# GSMLift.net
KiCad netlist of a schematic drawn in Altium Designer
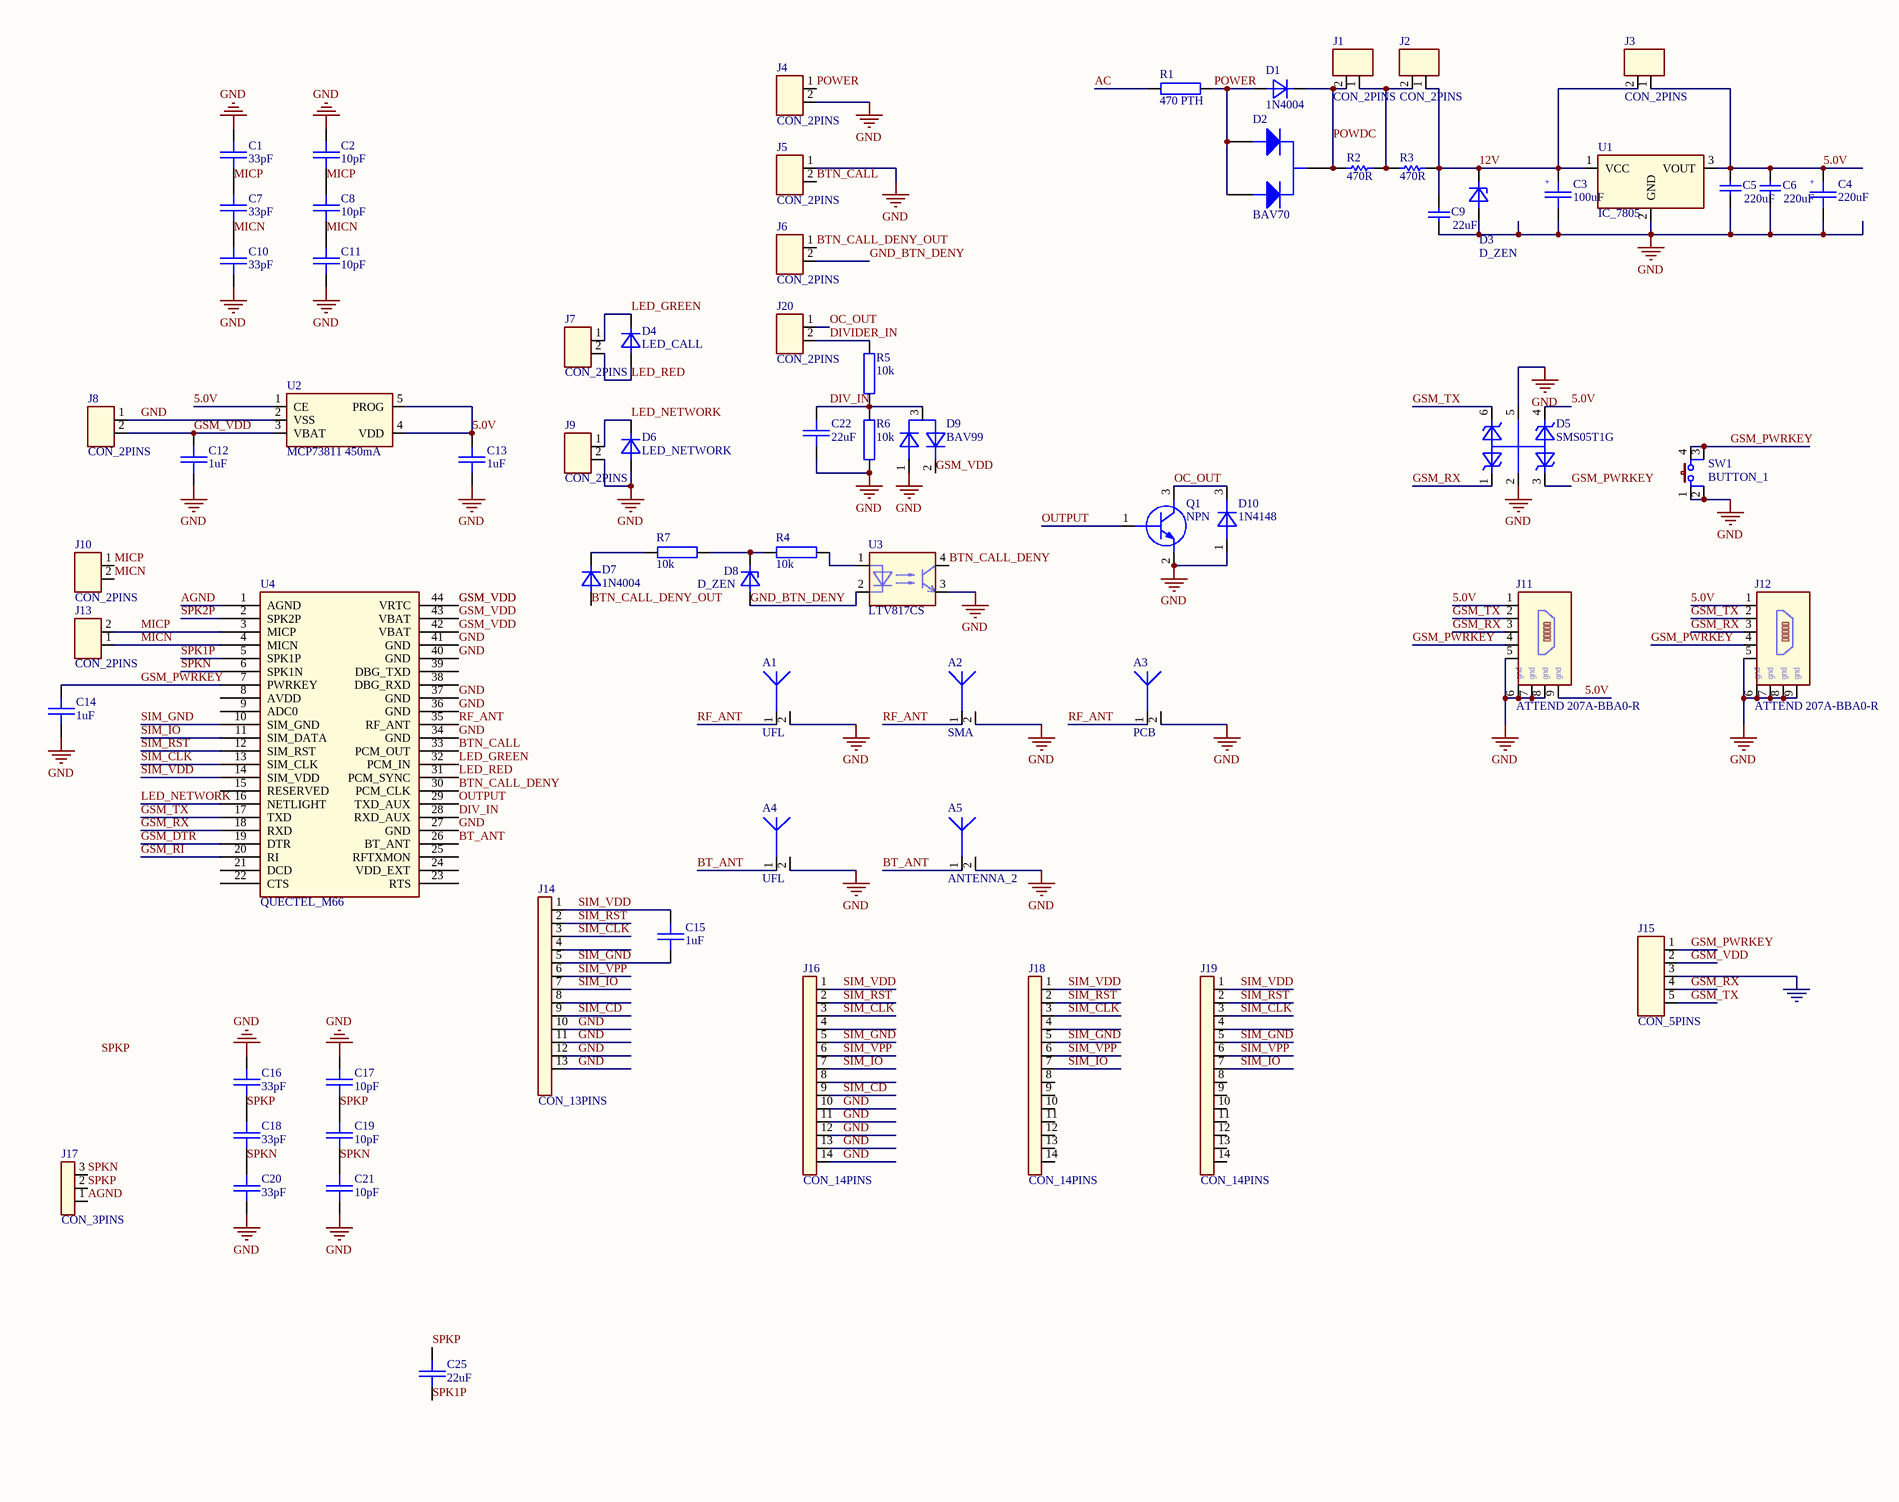
[diagram p0: GSMLift.SchDoc, left]
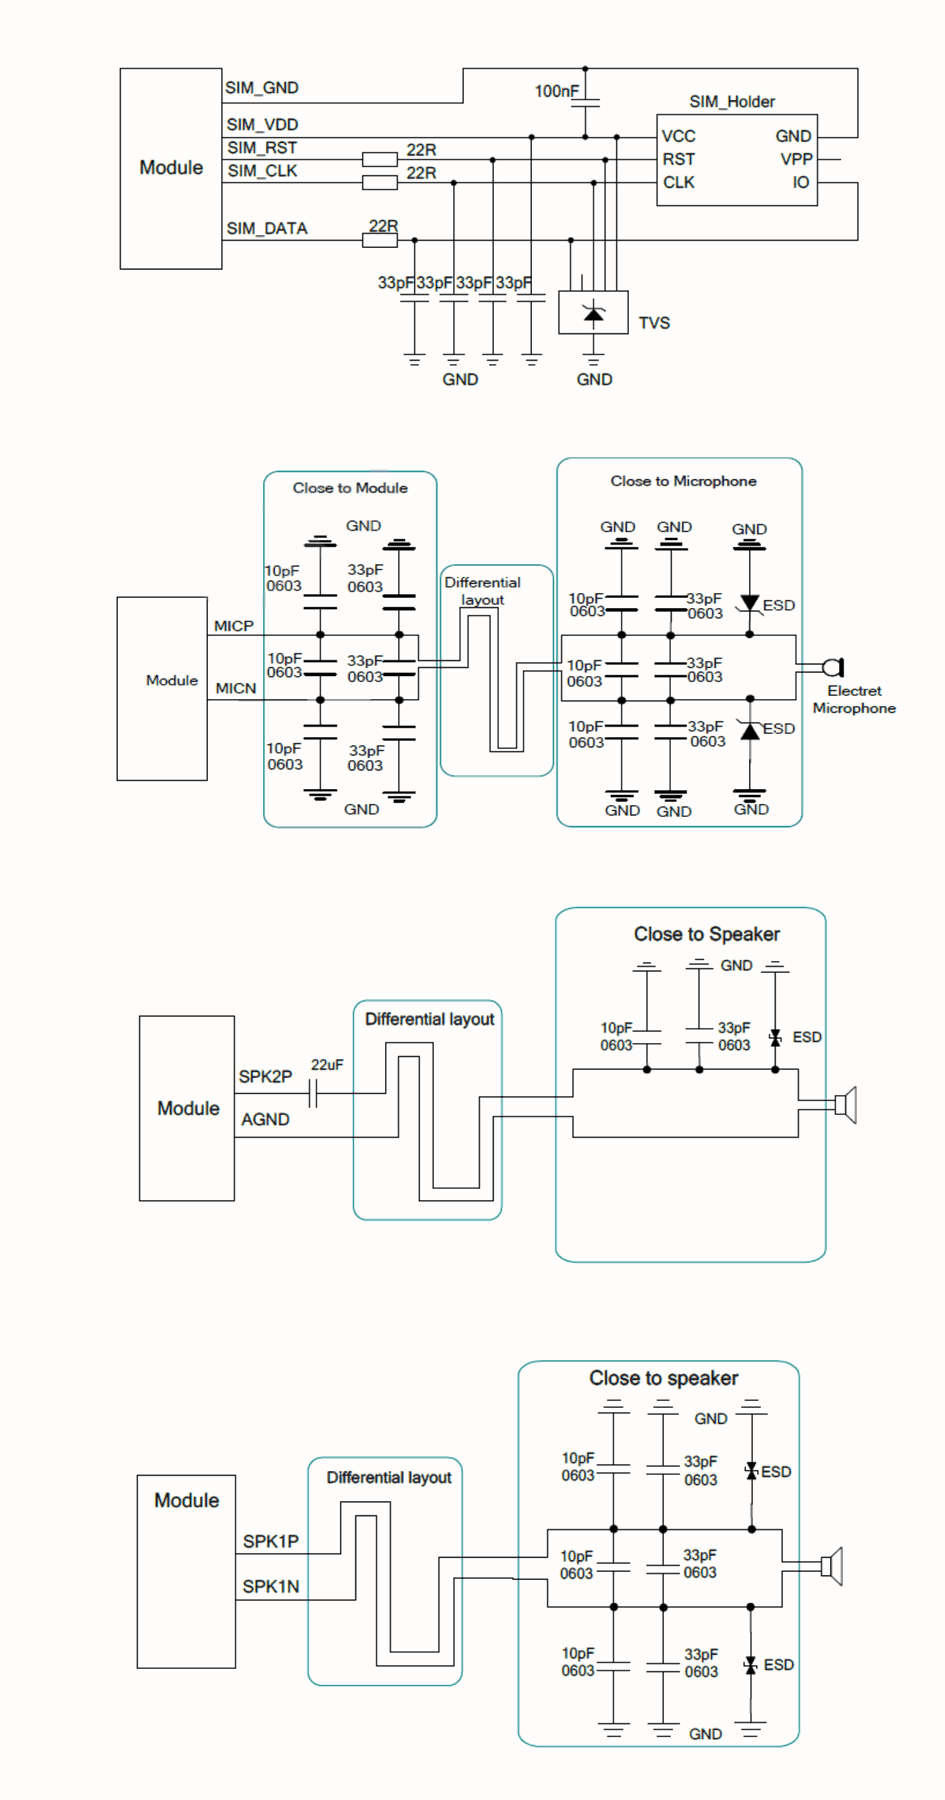
[diagram p1: GSMLift.SchDoc, right]

(export (version "E")
  (design (tool "Eeschema 10.0.6"))
  (components
    (comp (ref "A1")
      (value "UFL")
      (footprint "SMD_CON_ANTENNA_UFL")
      (libsource (lib "DLV") (part "ANTENNA_2"))
    )
    (comp (ref "A2")
      (value "SMA")
      (footprint "SMD_CON_ANTENNA_SMA")
      (libsource (lib "DLV") (part "ANTENNA_2"))
    )
    (comp (ref "A3")
      (value "PCB")
      (footprint "SMD_CON_ANTENNA_GSM_PCB_INV")
      (libsource (lib "DLV") (part "ANTENNA_2"))
    )
    (comp (ref "A4")
      (value "UFL")
      (footprint "SMD_CON_ANTENNA_UFL")
      (libsource (lib "DLV") (part "ANTENNA_2"))
    )
    (comp (ref "A5")
      (value "ANTENNA_2")
      (footprint "SMD_CON_ANTENNA_BT_PCB")
      (libsource (lib "DLV") (part "ANTENNA_2"))
    )
    (comp (ref "C1") (value "33pF") (footprint "SMD_0603_CAPC1608X95N") (libsource (lib "DLV") (part "C")))
    (comp (ref "C2") (value "10pF") (footprint "SMD_0603_CAPC1608X95N") (libsource (lib "DLV") (part "C")))
    (comp (ref "C3") (value "100uF") (footprint "SMD_CAPAE1030X1050N") (libsource (lib "DLV") (part "C_POL")))
    (comp (ref "C4") (value "220uF") (footprint "SMD_CAPAE1030X1050N") (libsource (lib "DLV") (part "C_POL")))
    (comp (ref "C5")
      (value "220uF")
      (footprint "SMD_1210_CAPC3225X279N")
      (description "CL32A227MQVNNNE 220UF 6.3V 20% X5R 1210")
      (fields (field (name "PUBLISHER") "Altium Limited"))
      (libsource (lib "Miscellaneous Devices") (part "Cap Semi"))
    )
    (comp (ref "C6")
      (value "220uF")
      (footprint "SMD_1210_CAPC3225X279N")
      (description "CL32A227MQVNNNE 220UF 6.3V 20% X5R 1210")
      (fields (field (name "PUBLISHER") "Altium Limited"))
      (libsource (lib "Miscellaneous Devices") (part "Cap Semi"))
    )
    (comp (ref "C7") (value "33pF") (footprint "SMD_0603_CAPC1608X95N") (libsource (lib "DLV") (part "C")))
    (comp (ref "C8") (value "10pF") (footprint "SMD_0603_CAPC1608X95N") (libsource (lib "DLV") (part "C")))
    (comp (ref "C9")
      (value "22uF")
      (footprint "SMD_1210_CAPC3225X279N")
      (description "CL32A227MQVNNNE 220UF 6.3V 20% X5R 1210")
      (fields (field (name "PUBLISHER") "Altium Limited"))
      (libsource (lib "Miscellaneous Devices") (part "Cap Semi"))
    )
    (comp (ref "C10") (value "33pF") (footprint "SMD_0603_CAPC1608X95N") (libsource (lib "DLV") (part "C")))
    (comp (ref "C11") (value "10pF") (footprint "SMD_0603_CAPC1608X95N") (libsource (lib "DLV") (part "C")))
    (comp (ref "C12") (value "1uF") (footprint "SMD_0603_CAPC1608X95N") (libsource (lib "DLV") (part "C")))
    (comp (ref "C13") (value "1uF") (footprint "SMD_0603_CAPC1608X95N") (libsource (lib "DLV") (part "C")))
    (comp (ref "C14") (value "1uF") (footprint "SMD_0603_CAPC1608X95N") (libsource (lib "DLV") (part "C")))
    (comp (ref "C15") (value "1uF") (footprint "SMD_0603_CAPC1608X95N") (libsource (lib "DLV") (part "C")))
    (comp (ref "C16") (value "33pF") (footprint "SMD_0603_CAPC1608X95N") (libsource (lib "DLV") (part "C")))
    (comp (ref "C17") (value "10pF") (footprint "SMD_0603_CAPC1608X95N") (libsource (lib "DLV") (part "C")))
    (comp (ref "C18") (value "33pF") (footprint "SMD_0603_CAPC1608X95N") (libsource (lib "DLV") (part "C")))
    (comp (ref "C19") (value "10pF") (footprint "SMD_0603_CAPC1608X95N") (libsource (lib "DLV") (part "C")))
    (comp (ref "C20") (value "33pF") (footprint "SMD_0603_CAPC1608X95N") (libsource (lib "DLV") (part "C")))
    (comp (ref "C21") (value "10pF") (footprint "SMD_0603_CAPC1608X95N") (libsource (lib "DLV") (part "C")))
    (comp (ref "C22") (value "22uF") (footprint "SMD_0805_CAPC2012X95N") (libsource (lib "DLV") (part "C")))
    (comp (ref "C25") (value "22uF") (footprint "SMD_0603_CAPC1608X95N") (libsource (lib "DLV") (part "C")))
    (comp (ref "D1")
      (value "1N4004")
      (footprint "SMD_DO214AC_SMA")
      (libsource (lib "EPIQ_DND_CIS_Library") (part "D"))
    )
    (comp (ref "D2")
      (value "BAV70")
      (footprint "SMD_SOT23_SOT95P240X120-3N")
      (libsource (lib "Devices") (part "DUAL DIODE BAV70"))
    )
    (comp (ref "D3")
      (value "D_ZEN")
      (footprint "SMD_DO214AC_SMA")
      (libsource (lib "EPIQ_DND_CIS_Library") (part "D_ZEN"))
    )
    (comp (ref "D4")
      (value "LED_CALL")
      (footprint "SMD_0805_LED2012X100N")
      (libsource (lib "DLV") (part "D"))
    )
    (comp (ref "D5")
      (value "SMS05T1G")
      (footprint "SMD_SOT95P280X145-6N-W")
      (description "4 IO lines TVS")
      (libsource (lib "BitCoin") (part "D_TVS_QUAD_C1AA2AA5C3C4C6"))
    )
    (comp (ref "D6")
      (value "LED_NETWORK")
      (footprint "SMD_0805_LED2012X100N")
      (libsource (lib "DLV") (part "D"))
    )
    (comp (ref "D7")
      (value "1N4004")
      (footprint "SMD_DO214AC_SMA")
      (libsource (lib "EPIQ_DND_CIS_Library") (part "D"))
    )
    (comp (ref "D8")
      (value "D_ZEN")
      (footprint "SMD_DO214AC_SMA")
      (libsource (lib "EPIQ_DND_CIS_Library") (part "D_ZEN"))
    )
    (comp (ref "D9")
      (value "BAV99")
      (footprint "SMD_SOT23_SOT95P240X120-3N")
      (libsource (lib "DLV") (part "D_DUAL_A1C2AC3"))
    )
    (comp (ref "D10")
      (value "1N4148")
      (footprint "SMD_SOT23_SOT95P240X120-3N")
      (libsource (lib "DLV") (part "D_A1C3"))
    )
    (comp (ref "J1")
      (value "CON_2PINS")
      (footprint "PTH_HDRV02W64P254_1X02")
      (libsource (lib "") (part "CON_2PINS_1"))
    )
    (comp (ref "J2")
      (value "CON_2PINS")
      (footprint "PTH_HDRV02W64P254_1X02")
      (libsource (lib "") (part "CON_2PINS_1"))
    )
    (comp (ref "J3")
      (value "CON_2PINS")
      (footprint "PTH_HDRV02W64P254_1X02")
      (libsource (lib "") (part "CON_2PINS_1"))
    )
    (comp (ref "J4")
      (value "CON_2PINS")
      (footprint "PTH_HDRV02W11060P500_1X02")
      (libsource (lib "DLV") (part "CON_2PINS"))
    )
    (comp (ref "J5")
      (value "CON_2PINS")
      (footprint "PTH_HDRV02W11060P500_1X02")
      (libsource (lib "DLV") (part "CON_2PINS"))
    )
    (comp (ref "J6")
      (value "CON_2PINS")
      (footprint "PTH_HDRV02W11060P500_1X02")
      (libsource (lib "DLV") (part "CON_2PINS"))
    )
    (comp (ref "J7")
      (value "CON_2PINS")
      (footprint "PTH_LED-KINGBRIGHT-L-934SGC")
      (libsource (lib "DLV") (part "CON_2PINS"))
    )
    (comp (ref "J8")
      (value "CON_2PINS")
      (footprint "PTH_HDRV02W64P254_1X02")
      (libsource (lib "DLV") (part "CON_2PINS"))
    )
    (comp (ref "J9")
      (value "CON_2PINS")
      (footprint "PTH_LED-KINGBRIGHT-L-934SGC")
      (libsource (lib "DLV") (part "CON_2PINS"))
    )
    (comp (ref "J10")
      (value "CON_2PINS")
      (footprint "PTH_HDRV02W11060P500_1X02")
      (libsource (lib "DLV") (part "CON_2PINS"))
    )
    (comp (ref "J11")
      (value "ATTEND 207A-BBA0-R")
      (footprint "SMD_CON_MICRO_USB")
      (libsource (lib "DLV") (part "CON_USB_MINI"))
    )
    (comp (ref "J12")
      (value "ATTEND 207A-BBA0-R")
      (footprint "SMD_CON-CVILUX-CU04-SCM15B0")
      (libsource (lib "DLV") (part "CON_USB_MINI"))
    )
    (comp (ref "J13")
      (value "CON_2PINS")
      (footprint "PTH_MIC_9.6MM_6MM_2.7MM_PITCH1.9 - duplicate")
      (libsource (lib "") (part "CON_2PINS_2"))
    )
    (comp (ref "J14")
      (value "CON_13PINS")
      (footprint "SMD_CON-ATTEND_MICRO_SIM_115Q-BCA0")
      (libsource (lib "DLV") (part "CON_13PINS"))
    )
    (comp (ref "J15") (value "CON_5PINS") (footprint "SIP5 - PGM") (libsource (lib "DLV") (part "CON_5PINS")))
    (comp (ref "J16")
      (value "CON_14PINS")
      (footprint "SMD_CON-ATTEND_SIM_115A-BDA0-R01")
      (libsource (lib "DLV") (part "CON_14PINS"))
    )
    (comp (ref "J17")
      (value "CON_3PINS")
      (footprint "PTH_HDRV03W11060P500_1X03")
      (libsource (lib "DLV") (part "CON_3PINS"))
    )
    (comp (ref "J18")
      (value "CON_14PINS")
      (footprint "SMD_CON-ATTEND_SIM_115B-AAA0-R01")
      (libsource (lib "DLV") (part "CON_14PINS"))
    )
    (comp (ref "J19")
      (value "CON_14PINS")
      (footprint "SMD_CON-ATTEND_SIM_115B-AAA0-R01")
      (libsource (lib "DLV") (part "CON_14PINS"))
    )
    (comp (ref "J20")
      (value "CON_2PINS")
      (footprint "PTH_HDRV02W11060P500_1X02")
      (libsource (lib "DLV") (part "CON_2PINS"))
    )
    (comp (ref "Q1")
      (value "NPN")
      (footprint "SMD_SOT23_SOT95P240X120-3N")
      (libsource (lib "DLV") (part "BJT_NPN_B1E2C3"))
    )
    (comp (ref "R1")
      (value "470 PTH")
      (footprint "PTH_RESAD2300W78L1750D650P")
      (libsource (lib "EPIQ_DND_CIS_Library") (part "R"))
    )
    (comp (ref "R2")
      (value "470R")
      (footprint "SMD_1206_RESC3216X102N")
      (description "Resistor")
      (fields
        (field (name "MANUFACTURER") "Generic Components")
        (field (name "PUBLISHER") "Altium Hobart Technology Centre")
      )
      (libsource (lib "Miscellaneous Devices") (part "Res1"))
    )
    (comp (ref "R3")
      (value "470R")
      (footprint "SMD_1206_RESC3216X102N")
      (description "Resistor")
      (fields
        (field (name "MANUFACTURER") "Generic Components")
        (field (name "PUBLISHER") "Altium Hobart Technology Centre")
      )
      (libsource (lib "Miscellaneous Devices") (part "Res1"))
    )
    (comp (ref "R4") (value "10k") (footprint "SMD_0603_RESC1608X55N") (libsource (lib "DLV") (part "R")))
    (comp (ref "R5") (value "10k") (footprint "SMD_0603_RESC1608X55N") (libsource (lib "DLV") (part "R")))
    (comp (ref "R6") (value "10k") (footprint "SMD_0805_RESC2012X60N") (libsource (lib "DLV") (part "R")))
    (comp (ref "R7") (value "10k") (footprint "SMD_1206_RESC3216X102N") (libsource (lib "DLV") (part "R")))
    (comp (ref "SW1")
      (value "BUTTON_1")
      (footprint "SMD_SW_TACT-64K")
      (libsource (lib "DLV") (part "BUTTON_1"))
    )
    (comp (ref "U1")
      (value "IC_7805")
      (footprint "SMD_TO254P1524X483-3_4N_D2PAK")
      (libsource (lib "DLV") (part "IC_7805"))
    )
    (comp (ref "U2")
      (value "MCP73811 450mA")
      (footprint "SMD_SOT26_SOT95P285X140-5N - DLV")
      (description "MCP73812")
      (fields
        (field (name "DB_PART_NUMBER") "PSU000000127")
        (field (name "DB_MANUFACTURER_PART") "ROHM        BD33KA5WF-E2")
        (field (name "DB_APPROVED_BY") "VSN")
      )
      (libsource (lib "DLV") (part "IC_MCP73812"))
    )
    (comp (ref "U3")
      (value "LTV817CS")
      (footprint "SMD_SOIC254P1030X390-4N")
      (libsource (lib "DLV") (part "OPTO_A1C2E3C4"))
    )
    (comp (ref "U4")
      (value "QUECTEL_M66")
      (footprint "SMD_MOD_M66-44N")
      (libsource (lib "DLV") (part "MOD_QUECTEL_M66"))
    )
  )
  (nets
    (net (code "1") (name "/5.0V") (class "Default")
      (node (ref "C13") (pin "1") (pinfunction "1_1") (pintype "passive"))
      (node (ref "C4") (pin "1") (pinfunction "1_1") (pintype "passive"))
      (node (ref "C5") (pin "1") (pinfunction "1_1") (pintype "passive"))
      (node (ref "C6") (pin "1") (pinfunction "1_1") (pintype "passive"))
      (node (ref "D5") (pin "4") (pinfunction "C3_4") (pintype "passive"))
      (node (ref "J11") (pin "1") (pinfunction "1_1") (pintype "passive"))
      (node (ref "J11") (pin "9") (pinfunction "9_9") (pintype "passive"))
      (node (ref "J12") (pin "1") (pinfunction "1_1") (pintype "passive"))
      (node (ref "J3") (pin "1") (pinfunction "1_1") (pintype "passive"))
      (node (ref "U1") (pin "3") (pinfunction "VOUT_3") (pintype "passive"))
      (node (ref "U2") (pin "1") (pinfunction "CE_1") (pintype "passive"))
      (node (ref "U2") (pin "4") (pinfunction "VDD_4") (pintype "passive"))
      (node (ref "U2") (pin "5") (pinfunction "PROG_5") (pintype "passive"))
    )
    (net (code "2") (name "/12V") (class "Default")
      (node (ref "C3") (pin "1") (pinfunction "1_1") (pintype "passive"))
      (node (ref "C9") (pin "1") (pinfunction "1_1") (pintype "passive"))
      (node (ref "D3") (pin "1") (pinfunction "C_1") (pintype "passive"))
      (node (ref "J2") (pin "1") (pinfunction "1_1") (pintype "passive"))
      (node (ref "J3") (pin "2") (pinfunction "2_2") (pintype "passive"))
      (node (ref "R3") (pin "2") (pinfunction "2_2") (pintype "passive"))
      (node (ref "U1") (pin "1") (pinfunction "VCC_1") (pintype "passive"))
    )
    (net (code "3") (name "/AC") (class "Default")
      (node (ref "R1") (pin "1") (pinfunction "1_1") (pintype "passive"))
    )
    (net (code "4") (name "/AGND") (class "Default")
      (node (ref "J17") (pin "1") (pinfunction "1_1") (pintype "passive"))
      (node (ref "U4") (pin "1") (pinfunction "AGND_1") (pintype "passive"))
    )
    (net (code "5") (name "/BTN_CALL") (class "Default")
      (node (ref "J5") (pin "2") (pinfunction "2_2") (pintype "passive"))
      (node (ref "U4") (pin "33") (pinfunction "PCM_OUT_33") (pintype "passive"))
    )
    (net (code "6") (name "/BTN_CALL_DENY") (class "Default")
      (node (ref "U3") (pin "4") (pinfunction "C_4") (pintype "passive"))
      (node (ref "U4") (pin "30") (pinfunction "PCM_CLK_30") (pintype "passive"))
    )
    (net (code "7") (name "/BTN_CALL_DENY_OUT") (class "Default")
      (node (ref "D7") (pin "2") (pinfunction "A_2") (pintype "passive"))
      (node (ref "J6") (pin "1") (pinfunction "1_1") (pintype "passive"))
    )
    (net (code "8") (name "/BT_ANT") (class "Default")
      (node (ref "A4") (pin "1") (pinfunction "1_1") (pintype "passive"))
      (node (ref "A5") (pin "1") (pinfunction "1_1") (pintype "passive"))
      (node (ref "U4") (pin "26") (pinfunction "BT_ANT_26") (pintype "passive"))
    )
    (net (code "9") (name "/DIVIDER_IN") (class "Default")
      (node (ref "J20") (pin "2") (pinfunction "2_2") (pintype "passive"))
      (node (ref "R5") (pin "2") (pinfunction "2_2") (pintype "passive"))
    )
    (net (code "10") (name "/DIV_IN") (class "Default")
      (node (ref "C22") (pin "1") (pinfunction "1_1") (pintype "passive"))
      (node (ref "D9") (pin "3") (pinfunction "AC_3") (pintype "passive"))
      (node (ref "R5") (pin "1") (pinfunction "1_1") (pintype "passive"))
      (node (ref "R6") (pin "1") (pinfunction "1_1") (pintype "passive"))
      (node (ref "U4") (pin "28") (pinfunction "RXD_AUX_28") (pintype "passive"))
    )
    (net (code "11") (name "/GND_BTN_DENY") (class "Default")
      (node (ref "D8") (pin "2") (pinfunction "A_2") (pintype "passive"))
      (node (ref "J6") (pin "2") (pinfunction "2_2") (pintype "passive"))
      (node (ref "U3") (pin "2") (pinfunction "C_2") (pintype "passive"))
    )
    (net (code "12") (name "/GSM_DTR") (class "Default")
      (node (ref "U4") (pin "19") (pinfunction "DTR_19") (pintype "passive"))
    )
    (net (code "13") (name "/GSM_PWRKEY") (class "Default")
      (node (ref "C14") (pin "1") (pinfunction "1_1") (pintype "passive"))
      (node (ref "D5") (pin "3") (pinfunction "C2_3") (pintype "passive"))
      (node (ref "J11") (pin "4") (pinfunction "4_4") (pintype "passive"))
      (node (ref "J12") (pin "4") (pinfunction "4_4") (pintype "passive"))
      (node (ref "J15") (pin "1") (pinfunction "1_1") (pintype "passive"))
      (node (ref "SW1") (pin "3") (pinfunction "3_3") (pintype "passive"))
      (node (ref "SW1") (pin "4") (pinfunction "4_4") (pintype "passive"))
      (node (ref "U4") (pin "7") (pinfunction "PWRKEY_7") (pintype "passive"))
    )
    (net (code "14") (name "/GSM_RI") (class "Default")
      (node (ref "U4") (pin "20") (pinfunction "RI_20") (pintype "passive"))
    )
    (net (code "15") (name "/GSM_RX") (class "Default")
      (node (ref "D5") (pin "1") (pinfunction "C1_1") (pintype "passive"))
      (node (ref "J11") (pin "3") (pinfunction "3_3") (pintype "passive"))
      (node (ref "J12") (pin "3") (pinfunction "3_3") (pintype "passive"))
      (node (ref "J15") (pin "4") (pinfunction "4_4") (pintype "passive"))
      (node (ref "U4") (pin "18") (pinfunction "RXD_18") (pintype "passive"))
    )
    (net (code "16") (name "/GSM_TX") (class "Default")
      (node (ref "D5") (pin "6") (pinfunction "C4_6") (pintype "passive"))
      (node (ref "J11") (pin "2") (pinfunction "2_2") (pintype "passive"))
      (node (ref "J12") (pin "2") (pinfunction "2_2") (pintype "passive"))
      (node (ref "J15") (pin "5") (pinfunction "5_5") (pintype "passive"))
      (node (ref "U4") (pin "17") (pinfunction "TXD_17") (pintype "passive"))
    )
    (net (code "17") (name "/GSM_VDD") (class "Default")
      (node (ref "C12") (pin "1") (pinfunction "1_1") (pintype "passive"))
      (node (ref "D9") (pin "2") (pinfunction "C_2") (pintype "passive"))
      (node (ref "J15") (pin "2") (pinfunction "2_2") (pintype "passive"))
      (node (ref "J8") (pin "2") (pinfunction "2_2") (pintype "passive"))
      (node (ref "U2") (pin "3") (pinfunction "VBAT_3") (pintype "passive"))
      (node (ref "U4") (pin "42") (pinfunction "VBAT_42") (pintype "passive"))
      (node (ref "U4") (pin "43") (pinfunction "VBAT_43") (pintype "passive"))
      (node (ref "U4") (pin "44") (pinfunction "VRTC_44") (pintype "passive"))
    )
    (net (code "18") (name "/LED_GREEN") (class "Default")
      (node (ref "D4") (pin "1") (pinfunction "C_1") (pintype "passive"))
      (node (ref "J7") (pin "1") (pinfunction "1_1") (pintype "passive"))
      (node (ref "U4") (pin "32") (pinfunction "PCM_IN_32") (pintype "passive"))
    )
    (net (code "19") (name "/LED_NETWORK") (class "Default")
      (node (ref "D6") (pin "1") (pinfunction "C_1") (pintype "passive"))
      (node (ref "J9") (pin "1") (pinfunction "1_1") (pintype "passive"))
      (node (ref "U4") (pin "16") (pinfunction "NETLIGHT_16") (pintype "passive"))
    )
    (net (code "20") (name "/LED_RED") (class "Default")
      (node (ref "D4") (pin "2") (pinfunction "A_2") (pintype "passive"))
      (node (ref "J7") (pin "2") (pinfunction "2_2") (pintype "passive"))
      (node (ref "U4") (pin "31") (pinfunction "PCM_SYNC_31") (pintype "passive"))
    )
    (net (code "21") (name "/MICN") (class "Default")
      (node (ref "C10") (pin "1") (pinfunction "1_1") (pintype "passive"))
      (node (ref "C11") (pin "1") (pinfunction "1_1") (pintype "passive"))
      (node (ref "C7") (pin "2") (pinfunction "2_2") (pintype "passive"))
      (node (ref "C8") (pin "2") (pinfunction "2_2") (pintype "passive"))
      (node (ref "J10") (pin "2") (pinfunction "2_2") (pintype "passive"))
      (node (ref "J13") (pin "1") (pinfunction "1_1") (pintype "passive"))
      (node (ref "U4") (pin "4") (pinfunction "MICN_4") (pintype "passive"))
    )
    (net (code "22") (name "/MICP") (class "Default")
      (node (ref "C1") (pin "2") (pinfunction "2_2") (pintype "passive"))
      (node (ref "C2") (pin "2") (pinfunction "2_2") (pintype "passive"))
      (node (ref "C7") (pin "1") (pinfunction "1_1") (pintype "passive"))
      (node (ref "C8") (pin "1") (pinfunction "1_1") (pintype "passive"))
      (node (ref "J10") (pin "1") (pinfunction "1_1") (pintype "passive"))
      (node (ref "J13") (pin "2") (pinfunction "2_2") (pintype "passive"))
      (node (ref "U4") (pin "3") (pinfunction "MICP_3") (pintype "passive"))
    )
    (net (code "23") (name "/OC_OUT") (class "Default")
      (node (ref "D10") (pin "3") (pinfunction "C_3") (pintype "passive"))
      (node (ref "J20") (pin "1") (pinfunction "1_1") (pintype "passive"))
      (node (ref "Q1") (pin "3") (pinfunction "C_3") (pintype "passive"))
    )
    (net (code "24") (name "/OUTPUT") (class "Default")
      (node (ref "Q1") (pin "1") (pinfunction "B_1") (pintype "passive"))
      (node (ref "U4") (pin "29") (pinfunction "TXD_AUX_29") (pintype "passive"))
    )
    (net (code "25") (name "/POWDC") (class "Default")
      (node (ref "D1") (pin "1") (pinfunction "C_1") (pintype "passive"))
      (node (ref "D2") (pin "3") (pinfunction "K_3") (pintype "passive"))
      (node (ref "J1") (pin "2") (pinfunction "2_2") (pintype "passive"))
      (node (ref "R2") (pin "1") (pinfunction "1_1") (pintype "passive"))
    )
    (net (code "26") (name "/POWER") (class "Default")
      (node (ref "D1") (pin "2") (pinfunction "A_2") (pintype "passive"))
      (node (ref "D2") (pin "1") (pinfunction "A1_1") (pintype "passive"))
      (node (ref "D2") (pin "2") (pinfunction "A2_2") (pintype "passive"))
      (node (ref "J4") (pin "1") (pinfunction "1_1") (pintype "passive"))
      (node (ref "R1") (pin "2") (pinfunction "2_2") (pintype "passive"))
    )
    (net (code "27") (name "/RF_ANT") (class "Default")
      (node (ref "A1") (pin "1") (pinfunction "1_1") (pintype "passive"))
      (node (ref "A2") (pin "1") (pinfunction "1_1") (pintype "passive"))
      (node (ref "A3") (pin "1") (pinfunction "1_1") (pintype "passive"))
      (node (ref "U4") (pin "35") (pinfunction "RF_ANT_35") (pintype "passive"))
    )
    (net (code "28") (name "/SIM_CD") (class "Default")
      (node (ref "J14") (pin "9") (pinfunction "9_9") (pintype "passive"))
      (node (ref "J16") (pin "9") (pinfunction "9_9") (pintype "passive"))
    )
    (net (code "29") (name "/SIM_CLK") (class "Default")
      (node (ref "J14") (pin "3") (pinfunction "3_3") (pintype "passive"))
      (node (ref "J16") (pin "3") (pinfunction "3_3") (pintype "passive"))
      (node (ref "J18") (pin "3") (pinfunction "3_3") (pintype "passive"))
      (node (ref "J19") (pin "3") (pinfunction "3_3") (pintype "passive"))
      (node (ref "U4") (pin "13") (pinfunction "SIM_CLK_13") (pintype "passive"))
    )
    (net (code "30") (name "/SIM_GND") (class "Default")
      (node (ref "C15") (pin "2") (pinfunction "2_2") (pintype "passive"))
      (node (ref "J14") (pin "5") (pinfunction "5_5") (pintype "passive"))
      (node (ref "J16") (pin "5") (pinfunction "5_5") (pintype "passive"))
      (node (ref "J18") (pin "5") (pinfunction "5_5") (pintype "passive"))
      (node (ref "J19") (pin "5") (pinfunction "5_5") (pintype "passive"))
      (node (ref "U4") (pin "10") (pinfunction "SIM_GND_10") (pintype "passive"))
    )
    (net (code "31") (name "/SIM_IO") (class "Default")
      (node (ref "J14") (pin "7") (pinfunction "7_7") (pintype "passive"))
      (node (ref "J16") (pin "7") (pinfunction "7_7") (pintype "passive"))
      (node (ref "J18") (pin "7") (pinfunction "7_7") (pintype "passive"))
      (node (ref "J19") (pin "7") (pinfunction "7_7") (pintype "passive"))
      (node (ref "U4") (pin "11") (pinfunction "SIM_DATA_11") (pintype "passive"))
    )
    (net (code "32") (name "/SIM_RST") (class "Default")
      (node (ref "J14") (pin "2") (pinfunction "2_2") (pintype "passive"))
      (node (ref "J16") (pin "2") (pinfunction "2_2") (pintype "passive"))
      (node (ref "J18") (pin "2") (pinfunction "2_2") (pintype "passive"))
      (node (ref "J19") (pin "2") (pinfunction "2_2") (pintype "passive"))
      (node (ref "U4") (pin "12") (pinfunction "SIM_RST_12") (pintype "passive"))
    )
    (net (code "33") (name "/SIM_VDD") (class "Default")
      (node (ref "C15") (pin "1") (pinfunction "1_1") (pintype "passive"))
      (node (ref "J14") (pin "1") (pinfunction "1_1") (pintype "passive"))
      (node (ref "J16") (pin "1") (pinfunction "1_1") (pintype "passive"))
      (node (ref "J18") (pin "1") (pinfunction "1_1") (pintype "passive"))
      (node (ref "J19") (pin "1") (pinfunction "1_1") (pintype "passive"))
      (node (ref "U4") (pin "14") (pinfunction "SIM_VDD_14") (pintype "passive"))
    )
    (net (code "34") (name "/SIM_VPP") (class "Default")
      (node (ref "J14") (pin "6") (pinfunction "6_6") (pintype "passive"))
      (node (ref "J16") (pin "6") (pinfunction "6_6") (pintype "passive"))
      (node (ref "J18") (pin "6") (pinfunction "6_6") (pintype "passive"))
      (node (ref "J19") (pin "6") (pinfunction "6_6") (pintype "passive"))
    )
    (net (code "35") (name "/SPK1P") (class "Default")
      (node (ref "C25") (pin "2") (pinfunction "2_2") (pintype "passive"))
      (node (ref "U4") (pin "5") (pinfunction "SPK1P_5") (pintype "passive"))
    )
    (net (code "36") (name "/SPK2P") (class "Default")
      (node (ref "U4") (pin "2") (pinfunction "SPK2P_2") (pintype "passive"))
    )
    (net (code "37") (name "/SPKN") (class "Default")
      (node (ref "C18") (pin "2") (pinfunction "2_2") (pintype "passive"))
      (node (ref "C19") (pin "2") (pinfunction "2_2") (pintype "passive"))
      (node (ref "C20") (pin "1") (pinfunction "1_1") (pintype "passive"))
      (node (ref "C21") (pin "1") (pinfunction "1_1") (pintype "passive"))
      (node (ref "J17") (pin "3") (pinfunction "3_3") (pintype "passive"))
      (node (ref "U4") (pin "6") (pinfunction "SPK1N_6") (pintype "passive"))
    )
    (net (code "38") (name "/SPKP") (class "Default")
      (node (ref "C16") (pin "2") (pinfunction "2_2") (pintype "passive"))
      (node (ref "C17") (pin "2") (pinfunction "2_2") (pintype "passive"))
      (node (ref "C18") (pin "1") (pinfunction "1_1") (pintype "passive"))
      (node (ref "C19") (pin "1") (pinfunction "1_1") (pintype "passive"))
      (node (ref "C25") (pin "1") (pinfunction "1_1") (pintype "passive"))
      (node (ref "J17") (pin "2") (pinfunction "2_2") (pintype "passive"))
    )
    (net (code "39") (name "GND") (class "Default")
      (node (ref "A1") (pin "2") (pinfunction "2_2") (pintype "passive"))
      (node (ref "A2") (pin "2") (pinfunction "2_2") (pintype "passive"))
      (node (ref "A3") (pin "2") (pinfunction "2_2") (pintype "passive"))
      (node (ref "A4") (pin "2") (pinfunction "2_2") (pintype "passive"))
      (node (ref "A5") (pin "2") (pinfunction "2_2") (pintype "passive"))
      (node (ref "C1") (pin "1") (pinfunction "1_1") (pintype "passive"))
      (node (ref "C10") (pin "2") (pinfunction "2_2") (pintype "passive"))
      (node (ref "C11") (pin "2") (pinfunction "2_2") (pintype "passive"))
      (node (ref "C12") (pin "2") (pinfunction "2_2") (pintype "passive"))
      (node (ref "C13") (pin "2") (pinfunction "2_2") (pintype "passive"))
      (node (ref "C14") (pin "2") (pinfunction "2_2") (pintype "passive"))
      (node (ref "C16") (pin "1") (pinfunction "1_1") (pintype "passive"))
      (node (ref "C17") (pin "1") (pinfunction "1_1") (pintype "passive"))
      (node (ref "C2") (pin "1") (pinfunction "1_1") (pintype "passive"))
      (node (ref "C20") (pin "2") (pinfunction "2_2") (pintype "passive"))
      (node (ref "C21") (pin "2") (pinfunction "2_2") (pintype "passive"))
      (node (ref "C22") (pin "2") (pinfunction "2_2") (pintype "passive"))
      (node (ref "C3") (pin "2") (pinfunction "2_2") (pintype "passive"))
      (node (ref "C4") (pin "2") (pinfunction "2_2") (pintype "passive"))
      (node (ref "C5") (pin "2") (pinfunction "2_2") (pintype "passive"))
      (node (ref "C6") (pin "2") (pinfunction "2_2") (pintype "passive"))
      (node (ref "C9") (pin "2") (pinfunction "2_2") (pintype "passive"))
      (node (ref "D10") (pin "1") (pinfunction "A_1") (pintype "passive"))
      (node (ref "D3") (pin "2") (pinfunction "A_2") (pintype "passive"))
      (node (ref "D5") (pin "2") (pinfunction "AAAA_2") (pintype "passive"))
      (node (ref "D5") (pin "5") (pinfunction "C4_5") (pintype "passive"))
      (node (ref "D6") (pin "2") (pinfunction "A_2") (pintype "passive"))
      (node (ref "D9") (pin "1") (pinfunction "A_1") (pintype "passive"))
      (node (ref "J11") (pin "5") (pinfunction "5_5") (pintype "passive"))
      (node (ref "J11") (pin "6") (pinfunction "6_6") (pintype "passive"))
      (node (ref "J11") (pin "7") (pinfunction "7_7") (pintype "passive"))
      (node (ref "J11") (pin "8") (pinfunction "8_8") (pintype "passive"))
      (node (ref "J12") (pin "5") (pinfunction "5_5") (pintype "passive"))
      (node (ref "J12") (pin "6") (pinfunction "6_6") (pintype "passive"))
      (node (ref "J12") (pin "7") (pinfunction "7_7") (pintype "passive"))
      (node (ref "J12") (pin "8") (pinfunction "8_8") (pintype "passive"))
      (node (ref "J12") (pin "9") (pinfunction "9_9") (pintype "passive"))
      (node (ref "J14") (pin "10") (pinfunction "10_10") (pintype "passive"))
      (node (ref "J14") (pin "11") (pinfunction "11_11") (pintype "passive"))
      (node (ref "J14") (pin "12") (pinfunction "12_12") (pintype "passive"))
      (node (ref "J14") (pin "13") (pinfunction "13_13") (pintype "passive"))
      (node (ref "J15") (pin "3") (pinfunction "3_3") (pintype "passive"))
      (node (ref "J16") (pin "10") (pinfunction "10_10") (pintype "passive"))
      (node (ref "J16") (pin "11") (pinfunction "11_11") (pintype "passive"))
      (node (ref "J16") (pin "12") (pinfunction "12_12") (pintype "passive"))
      (node (ref "J16") (pin "13") (pinfunction "13_13") (pintype "passive"))
      (node (ref "J16") (pin "14") (pinfunction "14_14") (pintype "passive"))
      (node (ref "J4") (pin "2") (pinfunction "2_2") (pintype "passive"))
      (node (ref "J5") (pin "1") (pinfunction "1_1") (pintype "passive"))
      (node (ref "J8") (pin "1") (pinfunction "1_1") (pintype "passive"))
      (node (ref "J9") (pin "2") (pinfunction "2_2") (pintype "passive"))
      (node (ref "Q1") (pin "2") (pinfunction "E_2") (pintype "passive"))
      (node (ref "R6") (pin "2") (pinfunction "2_2") (pintype "passive"))
      (node (ref "SW1") (pin "1") (pinfunction "1_1") (pintype "passive"))
      (node (ref "SW1") (pin "2") (pinfunction "2_2") (pintype "passive"))
      (node (ref "U1") (pin "2") (pinfunction "GND_2") (pintype "passive"))
      (node (ref "U2") (pin "2") (pinfunction "VSS_2") (pintype "passive"))
      (node (ref "U3") (pin "3") (pinfunction "E_3") (pintype "passive"))
      (node (ref "U4") (pin "27") (pinfunction "GND_27") (pintype "passive"))
      (node (ref "U4") (pin "34") (pinfunction "GND_34") (pintype "passive"))
      (node (ref "U4") (pin "36") (pinfunction "GND_36") (pintype "passive"))
      (node (ref "U4") (pin "37") (pinfunction "GND_37") (pintype "passive"))
      (node (ref "U4") (pin "40") (pinfunction "GND_40") (pintype "passive"))
      (node (ref "U4") (pin "41") (pinfunction "GND_41") (pintype "passive"))
    )
    (net (code "40") (name "Net-(D7-C)") (class "Default")
      (node (ref "D7") (pin "1") (pinfunction "C_1") (pintype "passive"))
      (node (ref "R7") (pin "1") (pinfunction "1_1") (pintype "passive"))
    )
    (net (code "41") (name "Net-(D8-C)") (class "Default")
      (node (ref "D8") (pin "1") (pinfunction "C_1") (pintype "passive"))
      (node (ref "R4") (pin "1") (pinfunction "1_1") (pintype "passive"))
      (node (ref "R7") (pin "2") (pinfunction "2_2") (pintype "passive"))
    )
    (net (code "42") (name "Net-(J1-Pad1)") (class "Default")
      (node (ref "J1") (pin "1") (pinfunction "1_1") (pintype "passive"))
      (node (ref "J2") (pin "2") (pinfunction "2_2") (pintype "passive"))
      (node (ref "R2") (pin "2") (pinfunction "2_2") (pintype "passive"))
      (node (ref "R3") (pin "1") (pinfunction "1_1") (pintype "passive"))
    )
    (net (code "43") (name "Net-(U3-A)") (class "Default")
      (node (ref "R4") (pin "2") (pinfunction "2_2") (pintype "passive"))
      (node (ref "U3") (pin "1") (pinfunction "A_1") (pintype "passive"))
    )
    (net (code "44") (name "unconnected-(J14-Pad4)") (class "Default")
      (node (ref "J14") (pin "4") (pinfunction "4_4") (pintype "passive"))
    )
    (net (code "45") (name "unconnected-(J14-Pad8)") (class "Default")
      (node (ref "J14") (pin "8") (pinfunction "8_8") (pintype "passive"))
    )
    (net (code "46") (name "unconnected-(J16-Pad4)") (class "Default")
      (node (ref "J16") (pin "4") (pinfunction "4_4") (pintype "passive"))
    )
    (net (code "47") (name "unconnected-(J16-Pad8)") (class "Default")
      (node (ref "J16") (pin "8") (pinfunction "8_8") (pintype "passive"))
    )
    (net (code "48") (name "unconnected-(J18-Pad4)") (class "Default")
      (node (ref "J18") (pin "4") (pinfunction "4_4") (pintype "passive"))
    )
    (net (code "49") (name "unconnected-(J18-Pad8)") (class "Default")
      (node (ref "J18") (pin "8") (pinfunction "8_8") (pintype "passive"))
    )
    (net (code "50") (name "unconnected-(J18-Pad9)") (class "Default")
      (node (ref "J18") (pin "9") (pinfunction "9_9") (pintype "passive"))
    )
    (net (code "51") (name "unconnected-(J18-Pad10)") (class "Default")
      (node (ref "J18") (pin "10") (pinfunction "10_10") (pintype "passive"))
    )
    (net (code "52") (name "unconnected-(J18-Pad11)") (class "Default")
      (node (ref "J18") (pin "11") (pinfunction "11_11") (pintype "passive"))
    )
    (net (code "53") (name "unconnected-(J18-Pad12)") (class "Default")
      (node (ref "J18") (pin "12") (pinfunction "12_12") (pintype "passive"))
    )
    (net (code "54") (name "unconnected-(J18-Pad13)") (class "Default")
      (node (ref "J18") (pin "13") (pinfunction "13_13") (pintype "passive"))
    )
    (net (code "55") (name "unconnected-(J18-Pad14)") (class "Default")
      (node (ref "J18") (pin "14") (pinfunction "14_14") (pintype "passive"))
    )
    (net (code "56") (name "unconnected-(J19-Pad4)") (class "Default")
      (node (ref "J19") (pin "4") (pinfunction "4_4") (pintype "passive"))
    )
    (net (code "57") (name "unconnected-(J19-Pad8)") (class "Default")
      (node (ref "J19") (pin "8") (pinfunction "8_8") (pintype "passive"))
    )
    (net (code "58") (name "unconnected-(J19-Pad9)") (class "Default")
      (node (ref "J19") (pin "9") (pinfunction "9_9") (pintype "passive"))
    )
    (net (code "59") (name "unconnected-(J19-Pad10)") (class "Default")
      (node (ref "J19") (pin "10") (pinfunction "10_10") (pintype "passive"))
    )
    (net (code "60") (name "unconnected-(J19-Pad11)") (class "Default")
      (node (ref "J19") (pin "11") (pinfunction "11_11") (pintype "passive"))
    )
    (net (code "61") (name "unconnected-(J19-Pad12)") (class "Default")
      (node (ref "J19") (pin "12") (pinfunction "12_12") (pintype "passive"))
    )
    (net (code "62") (name "unconnected-(J19-Pad13)") (class "Default")
      (node (ref "J19") (pin "13") (pinfunction "13_13") (pintype "passive"))
    )
    (net (code "63") (name "unconnected-(J19-Pad14)") (class "Default")
      (node (ref "J19") (pin "14") (pinfunction "14_14") (pintype "passive"))
    )
    (net (code "64") (name "unconnected-(U4-ADC0-Pad9)") (class "Default")
      (node (ref "U4") (pin "9") (pinfunction "ADC0_9") (pintype "passive"))
    )
    (net (code "65") (name "unconnected-(U4-AVDD-Pad8)") (class "Default")
      (node (ref "U4") (pin "8") (pinfunction "AVDD_8") (pintype "passive"))
    )
    (net (code "66") (name "unconnected-(U4-CTS-Pad22)") (class "Default")
      (node (ref "U4") (pin "22") (pinfunction "CTS_22") (pintype "passive"))
    )
    (net (code "67") (name "unconnected-(U4-DBG_RXD-Pad38)") (class "Default")
      (node (ref "U4") (pin "38") (pinfunction "DBG_RXD_38") (pintype "passive"))
    )
    (net (code "68") (name "unconnected-(U4-DBG_TXD-Pad39)") (class "Default")
      (node (ref "U4") (pin "39") (pinfunction "DBG_TXD_39") (pintype "passive"))
    )
    (net (code "69") (name "unconnected-(U4-DCD-Pad21)") (class "Default")
      (node (ref "U4") (pin "21") (pinfunction "DCD_21") (pintype "passive"))
    )
    (net (code "70") (name "unconnected-(U4-RESERVED-Pad15)") (class "Default")
      (node (ref "U4") (pin "15") (pinfunction "RESERVED_15") (pintype "passive"))
    )
    (net (code "71") (name "unconnected-(U4-RFTXMON-Pad25)") (class "Default")
      (node (ref "U4") (pin "25") (pinfunction "RFTXMON_25") (pintype "passive"))
    )
    (net (code "72") (name "unconnected-(U4-RTS-Pad23)") (class "Default")
      (node (ref "U4") (pin "23") (pinfunction "RTS_23") (pintype "passive"))
    )
    (net (code "73") (name "unconnected-(U4-VDD_EXT-Pad24)") (class "Default")
      (node (ref "U4") (pin "24") (pinfunction "VDD_EXT_24") (pintype "passive"))
    )
  )
)
